# Composite-Module.net
KiCad netlist of a schematic drawn in Altium Designer
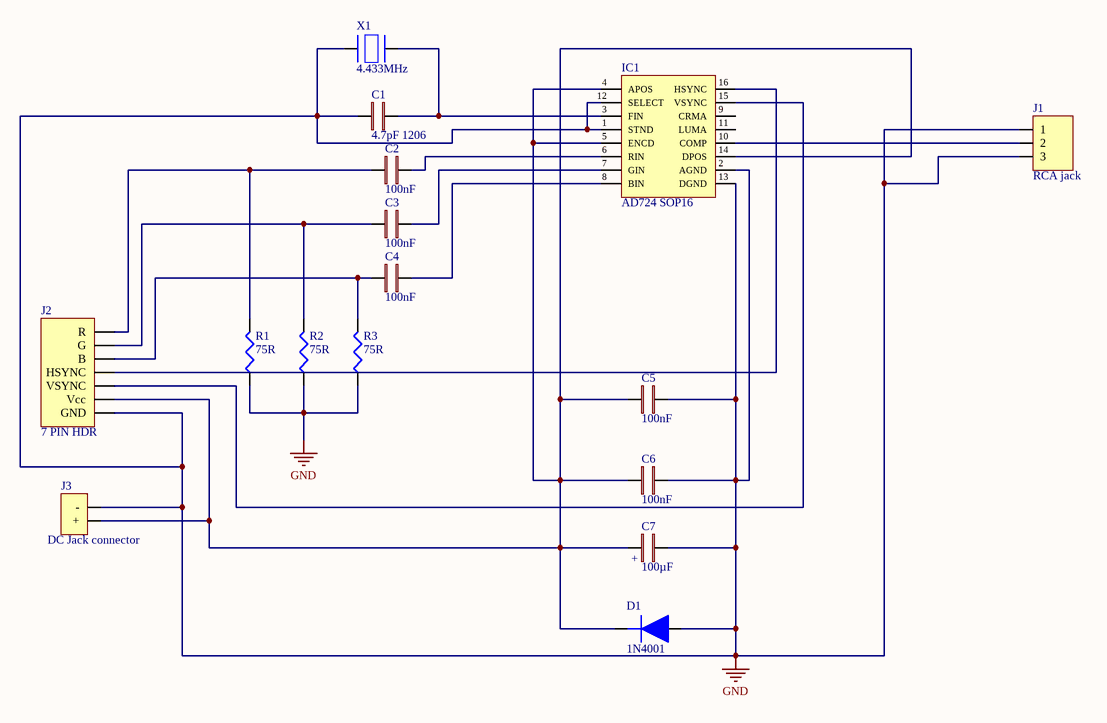
[diagram p0: Composite-Module.SchDoc]

(export (version "E")
  (design (tool "Eeschema 10.0.6"))
  (components
    (comp (ref "C1")
      (value "4.7pF 1206")
      (footprint "CAPACITOR 1206")
      (description "1206 4.7 pF 50 V ±0.25 pF Tolerance C0G/NP0 SMT Multilayer Ceramic Capacitor")
      (fields
        (field (name "MANUFACTURER") "Kyocera AVX")
        (field (name "MANUFACTURER PART NUMBER") "12065A4R7CAT2A")
      )
      (libsource (lib "AGES") (part "Capacitor{colon} 4.7pF"))
    )
    (comp (ref "C2")
      (value "100nF")
      (footprint "CAPACITOR 1206")
      (description "Ceramic capacitor SMD-1206 100nF /50V X7R# K +-10%, AVX, RoHS, /4000 reel/")
      (fields
        (field (name "MANUFACTURER") "Kyocera AVX")
        (field (name "MANUFACTURER PART NUMBER") "12065C104KAT2A")
      )
      (libsource (lib "AGES") (part "Capacitor{colon} 100nF"))
    )
    (comp (ref "C3")
      (value "100nF")
      (footprint "CAPACITOR 1206")
      (description "Ceramic capacitor SMD-1206 100nF /50V X7R# K +-10%, AVX, RoHS, /4000 reel/")
      (fields
        (field (name "MANUFACTURER") "Kyocera AVX")
        (field (name "MANUFACTURER PART NUMBER") "12065C104KAT2A")
      )
      (libsource (lib "AGES") (part "Capacitor{colon} 100nF"))
    )
    (comp (ref "C4")
      (value "100nF")
      (footprint "CAPACITOR 1206")
      (description "Ceramic capacitor SMD-1206 100nF /50V X7R# K +-10%, AVX, RoHS, /4000 reel/")
      (fields
        (field (name "MANUFACTURER") "Kyocera AVX")
        (field (name "MANUFACTURER PART NUMBER") "12065C104KAT2A")
      )
      (libsource (lib "AGES") (part "Capacitor{colon} 100nF"))
    )
    (comp (ref "C5")
      (value "100nF")
      (footprint "CAPACITOR 1206")
      (description "Ceramic capacitor SMD-1206 100nF /50V X7R# K +-10%, AVX, RoHS, /4000 reel/")
      (fields
        (field (name "MANUFACTURER") "Kyocera AVX")
        (field (name "MANUFACTURER PART NUMBER") "12065C104KAT2A")
      )
      (libsource (lib "AGES") (part "Capacitor{colon} 100nF"))
    )
    (comp (ref "C6")
      (value "100nF")
      (footprint "CAPACITOR 1206")
      (description "Ceramic capacitor SMD-1206 100nF /50V X7R# K +-10%, AVX, RoHS, /4000 reel/")
      (fields
        (field (name "MANUFACTURER") "Kyocera AVX")
        (field (name "MANUFACTURER PART NUMBER") "12065C104KAT2A")
      )
      (libsource (lib "AGES") (part "Capacitor{colon} 100nF"))
    )
    (comp (ref "C7")
      (value "100µF")
      (footprint "ELCO")
      (description "CAP ALUM 100UF 20% 10V SMD")
      (fields
        (field (name "MANUFACTURER") "Panasonic")
        (field (name "MANUFACTURER PART NUMBER") "EEE-1AA101WR")
      )
      (libsource (lib "AGES") (part "Capacitor{colon} 100µF (elco)"))
    )
    (comp (ref "D1")
      (value "1N4001")
      (footprint "DIODE")
      (description "Rectifier Diode Switching 100V 1A 2000ns 2-Pin SMA T/R")
      (fields (field (name "MANUFACTURER") "MCC") (field (name "MANUFACTURER PART NUMBER") "GS1B-LTP"))
      (libsource (lib "AGES") (part "Diode{colon} 1N4001"))
    )
    (comp (ref "IC1")
      (value "AD724 SOP16")
      (footprint "AD724")
      (description "RGB to NTSC and PAL Encoder 16-Pin SOIC W Tube")
      (fields
        (field (name "MANUFACTURER") "Analog Devices")
        (field (name "MANUFACTURER PART NUMBER") "AD724JRZ")
      )
      (libsource (lib "AGES") (part "IC{colon} AD724"))
    )
    (comp (ref "J1")
      (value "RCA jack")
      (footprint "RCA JACK")
      (description "Conn RCA RCP 4 POS Solder RA SMD 2 Terminal 1 Port T/R")
      (fields (field (name "MANUFACTURER") "CUI") (field (name "MANUFACTURER PART NUMBER") "RCJ-014-SMT-TR"))
      (libsource (lib "Composite-Module") (part "Connector{colon} RCA female"))
    )
    (comp (ref "J2")
      (value "7 PIN HDR")
      (footprint "7 HDR")
      (description "7 pin header")
      (libsource (lib "Composite-Module") (part "CONNECTOR{colon} 7 PIN HDR"))
    )
    (comp (ref "J3")
      (value "DC Jack connector")
      (footprint "DC JACK")
      (description "2.0 x 6.5 mm, 2.5 A, Horizontal, Through Hole, Dc Power Jack Connector")
      (fields (field (name "MANUFACTURER") "CUI") (field (name "MANUFACTURER PART NUMBER") "PJ-002A"))
      (libsource (lib "Composite-Module") (part "Connector{colon} DC Jack"))
    )
    (comp (ref "R1")
      (value "75R")
      (footprint "Resistor 1206")
      (description "Res Thin Film 1206 75 Ohm 0.1% 1/4W ±25ppm/°C Molded SMD SMD Punched Carrier T/R")
      (fields
        (field (name "MANUFACTURER") "Panasonic")
        (field (name "MANUFACTURER PART NUMBER") "ERA-8AEB750V")
      )
      (libsource (lib "AGES") (part "Resistor{colon} 75R"))
    )
    (comp (ref "R2")
      (value "75R")
      (footprint "Resistor 1206")
      (description "Res Thin Film 1206 75 Ohm 0.1% 1/4W ±25ppm/°C Molded SMD SMD Punched Carrier T/R")
      (fields
        (field (name "MANUFACTURER") "Panasonic")
        (field (name "MANUFACTURER PART NUMBER") "ERA-8AEB750V")
      )
      (libsource (lib "AGES") (part "Resistor{colon} 75R"))
    )
    (comp (ref "R3")
      (value "75R")
      (footprint "Resistor 1206")
      (description "Res Thin Film 1206 75 Ohm 0.1% 1/4W ±25ppm/°C Molded SMD SMD Punched Carrier T/R")
      (fields
        (field (name "MANUFACTURER") "Panasonic")
        (field (name "MANUFACTURER PART NUMBER") "ERA-8AEB750V")
      )
      (libsource (lib "AGES") (part "Resistor{colon} 75R"))
    )
    (comp (ref "X1")
      (value "4.433MHz")
      (footprint "XTAL 4.4436 MHz")
      (description "Crystal 10MHz 30pF 2-Pin HC-49/U Loose")
      (fields
        (field (name "MANUFACTURER") "Multicomp")
        (field (name "MANUFACTURER PART NUMBER") "HC49S-10-30-50-70-30-ATF")
      )
      (libsource (lib "AGES") (part "Crystal{colon} 4.433MHz"))
    )
  )
  (nets
    (net (code "1") (name "GND") (class "Default")
      (node (ref "C1") (pin "2") (pinfunction "2_2") (pintype "passive"))
      (node (ref "C5") (pin "1") (pinfunction "1_1") (pintype "passive"))
      (node (ref "C6") (pin "1") (pinfunction "1_1") (pintype "passive"))
      (node (ref "C7") (pin "2") (pinfunction "-_2") (pintype "passive"))
      (node (ref "D1") (pin "1") (pinfunction "1_1") (pintype "passive"))
      (node (ref "IC1") (pin "1") (pinfunction "STND_1") (pintype "passive"))
      (node (ref "IC1") (pin "12") (pinfunction "SELECT_12") (pintype "passive"))
      (node (ref "IC1") (pin "13") (pinfunction "DGND_13") (pintype "passive"))
      (node (ref "IC1") (pin "2") (pinfunction "AGND_2") (pintype "passive"))
      (node (ref "J1") (pin "1") (pinfunction "1_1") (pintype "passive"))
      (node (ref "J1") (pin "3") (pinfunction "3_3") (pintype "passive"))
      (node (ref "J2") (pin "7") (pinfunction "GND_7") (pintype "passive"))
      (node (ref "J3") (pin "2") (pinfunction "-_2") (pintype "passive"))
      (node (ref "R1") (pin "1") (pinfunction "1_1") (pintype "passive"))
      (node (ref "R2") (pin "1") (pinfunction "1_1") (pintype "passive"))
      (node (ref "R3") (pin "1") (pinfunction "1_1") (pintype "passive"))
      (node (ref "X1") (pin "2") (pinfunction "2_2") (pintype "passive"))
    )
    (net (code "2") (name "Net-(C7-+)") (class "Default")
      (node (ref "C5") (pin "2") (pinfunction "2_2") (pintype "passive"))
      (node (ref "C6") (pin "2") (pinfunction "2_2") (pintype "passive"))
      (node (ref "C7") (pin "1") (pinfunction "+_1") (pintype "passive"))
      (node (ref "D1") (pin "2") (pinfunction "2_2") (pintype "passive"))
      (node (ref "IC1") (pin "14") (pinfunction "DPOS_14") (pintype "passive"))
      (node (ref "IC1") (pin "4") (pinfunction "APOS_4") (pintype "passive"))
      (node (ref "IC1") (pin "5") (pinfunction "ENCD_5") (pintype "passive"))
      (node (ref "J2") (pin "6") (pinfunction "Vcc_6") (pintype "passive"))
      (node (ref "J3") (pin "1") (pinfunction "+_1") (pintype "passive"))
    )
    (net (code "3") (name "Net-(IC1-BIN)") (class "Default")
      (node (ref "C4") (pin "1") (pinfunction "1_1") (pintype "passive"))
      (node (ref "IC1") (pin "8") (pinfunction "BIN_8") (pintype "passive"))
    )
    (net (code "4") (name "Net-(IC1-COMP)") (class "Default")
      (node (ref "IC1") (pin "10") (pinfunction "COMP_10") (pintype "passive"))
      (node (ref "J1") (pin "2") (pinfunction "2_2") (pintype "passive"))
    )
    (net (code "5") (name "Net-(IC1-FIN)") (class "Default")
      (node (ref "C1") (pin "1") (pinfunction "1_1") (pintype "passive"))
      (node (ref "IC1") (pin "3") (pinfunction "FIN_3") (pintype "passive"))
      (node (ref "X1") (pin "1") (pinfunction "1_1") (pintype "passive"))
    )
    (net (code "6") (name "Net-(IC1-GIN)") (class "Default")
      (node (ref "C3") (pin "1") (pinfunction "1_1") (pintype "passive"))
      (node (ref "IC1") (pin "7") (pinfunction "GIN_7") (pintype "passive"))
    )
    (net (code "7") (name "Net-(IC1-HSYNC)") (class "Default")
      (node (ref "IC1") (pin "16") (pinfunction "HSYNC_16") (pintype "passive"))
      (node (ref "J2") (pin "4") (pinfunction "HSYNC_4") (pintype "passive"))
    )
    (net (code "8") (name "Net-(IC1-RIN)") (class "Default")
      (node (ref "C2") (pin "1") (pinfunction "1_1") (pintype "passive"))
      (node (ref "IC1") (pin "6") (pinfunction "RIN_6") (pintype "passive"))
    )
    (net (code "9") (name "Net-(IC1-VSYNC)") (class "Default")
      (node (ref "IC1") (pin "15") (pinfunction "VSYNC_15") (pintype "passive"))
      (node (ref "J2") (pin "5") (pinfunction "VSYNC_5") (pintype "passive"))
    )
    (net (code "10") (name "Net-(J2-B)") (class "Default")
      (node (ref "C4") (pin "2") (pinfunction "2_2") (pintype "passive"))
      (node (ref "J2") (pin "3") (pinfunction "B_3") (pintype "passive"))
      (node (ref "R3") (pin "2") (pinfunction "2_2") (pintype "passive"))
    )
    (net (code "11") (name "Net-(J2-G)") (class "Default")
      (node (ref "C3") (pin "2") (pinfunction "2_2") (pintype "passive"))
      (node (ref "J2") (pin "2") (pinfunction "G_2") (pintype "passive"))
      (node (ref "R2") (pin "2") (pinfunction "2_2") (pintype "passive"))
    )
    (net (code "12") (name "Net-(J2-R)") (class "Default")
      (node (ref "C2") (pin "2") (pinfunction "2_2") (pintype "passive"))
      (node (ref "J2") (pin "1") (pinfunction "R_1") (pintype "passive"))
      (node (ref "R1") (pin "2") (pinfunction "2_2") (pintype "passive"))
    )
    (net (code "13") (name "unconnected-(IC1-CRMA-Pad9)") (class "Default")
      (node (ref "IC1") (pin "9") (pinfunction "CRMA_9") (pintype "passive"))
    )
    (net (code "14") (name "unconnected-(IC1-LUMA-Pad11)") (class "Default")
      (node (ref "IC1") (pin "11") (pinfunction "LUMA_11") (pintype "passive"))
    )
  )
)
